# PCB-ATEM-GPITBO2.net
KiCad netlist of a schematic drawn in EAGLE
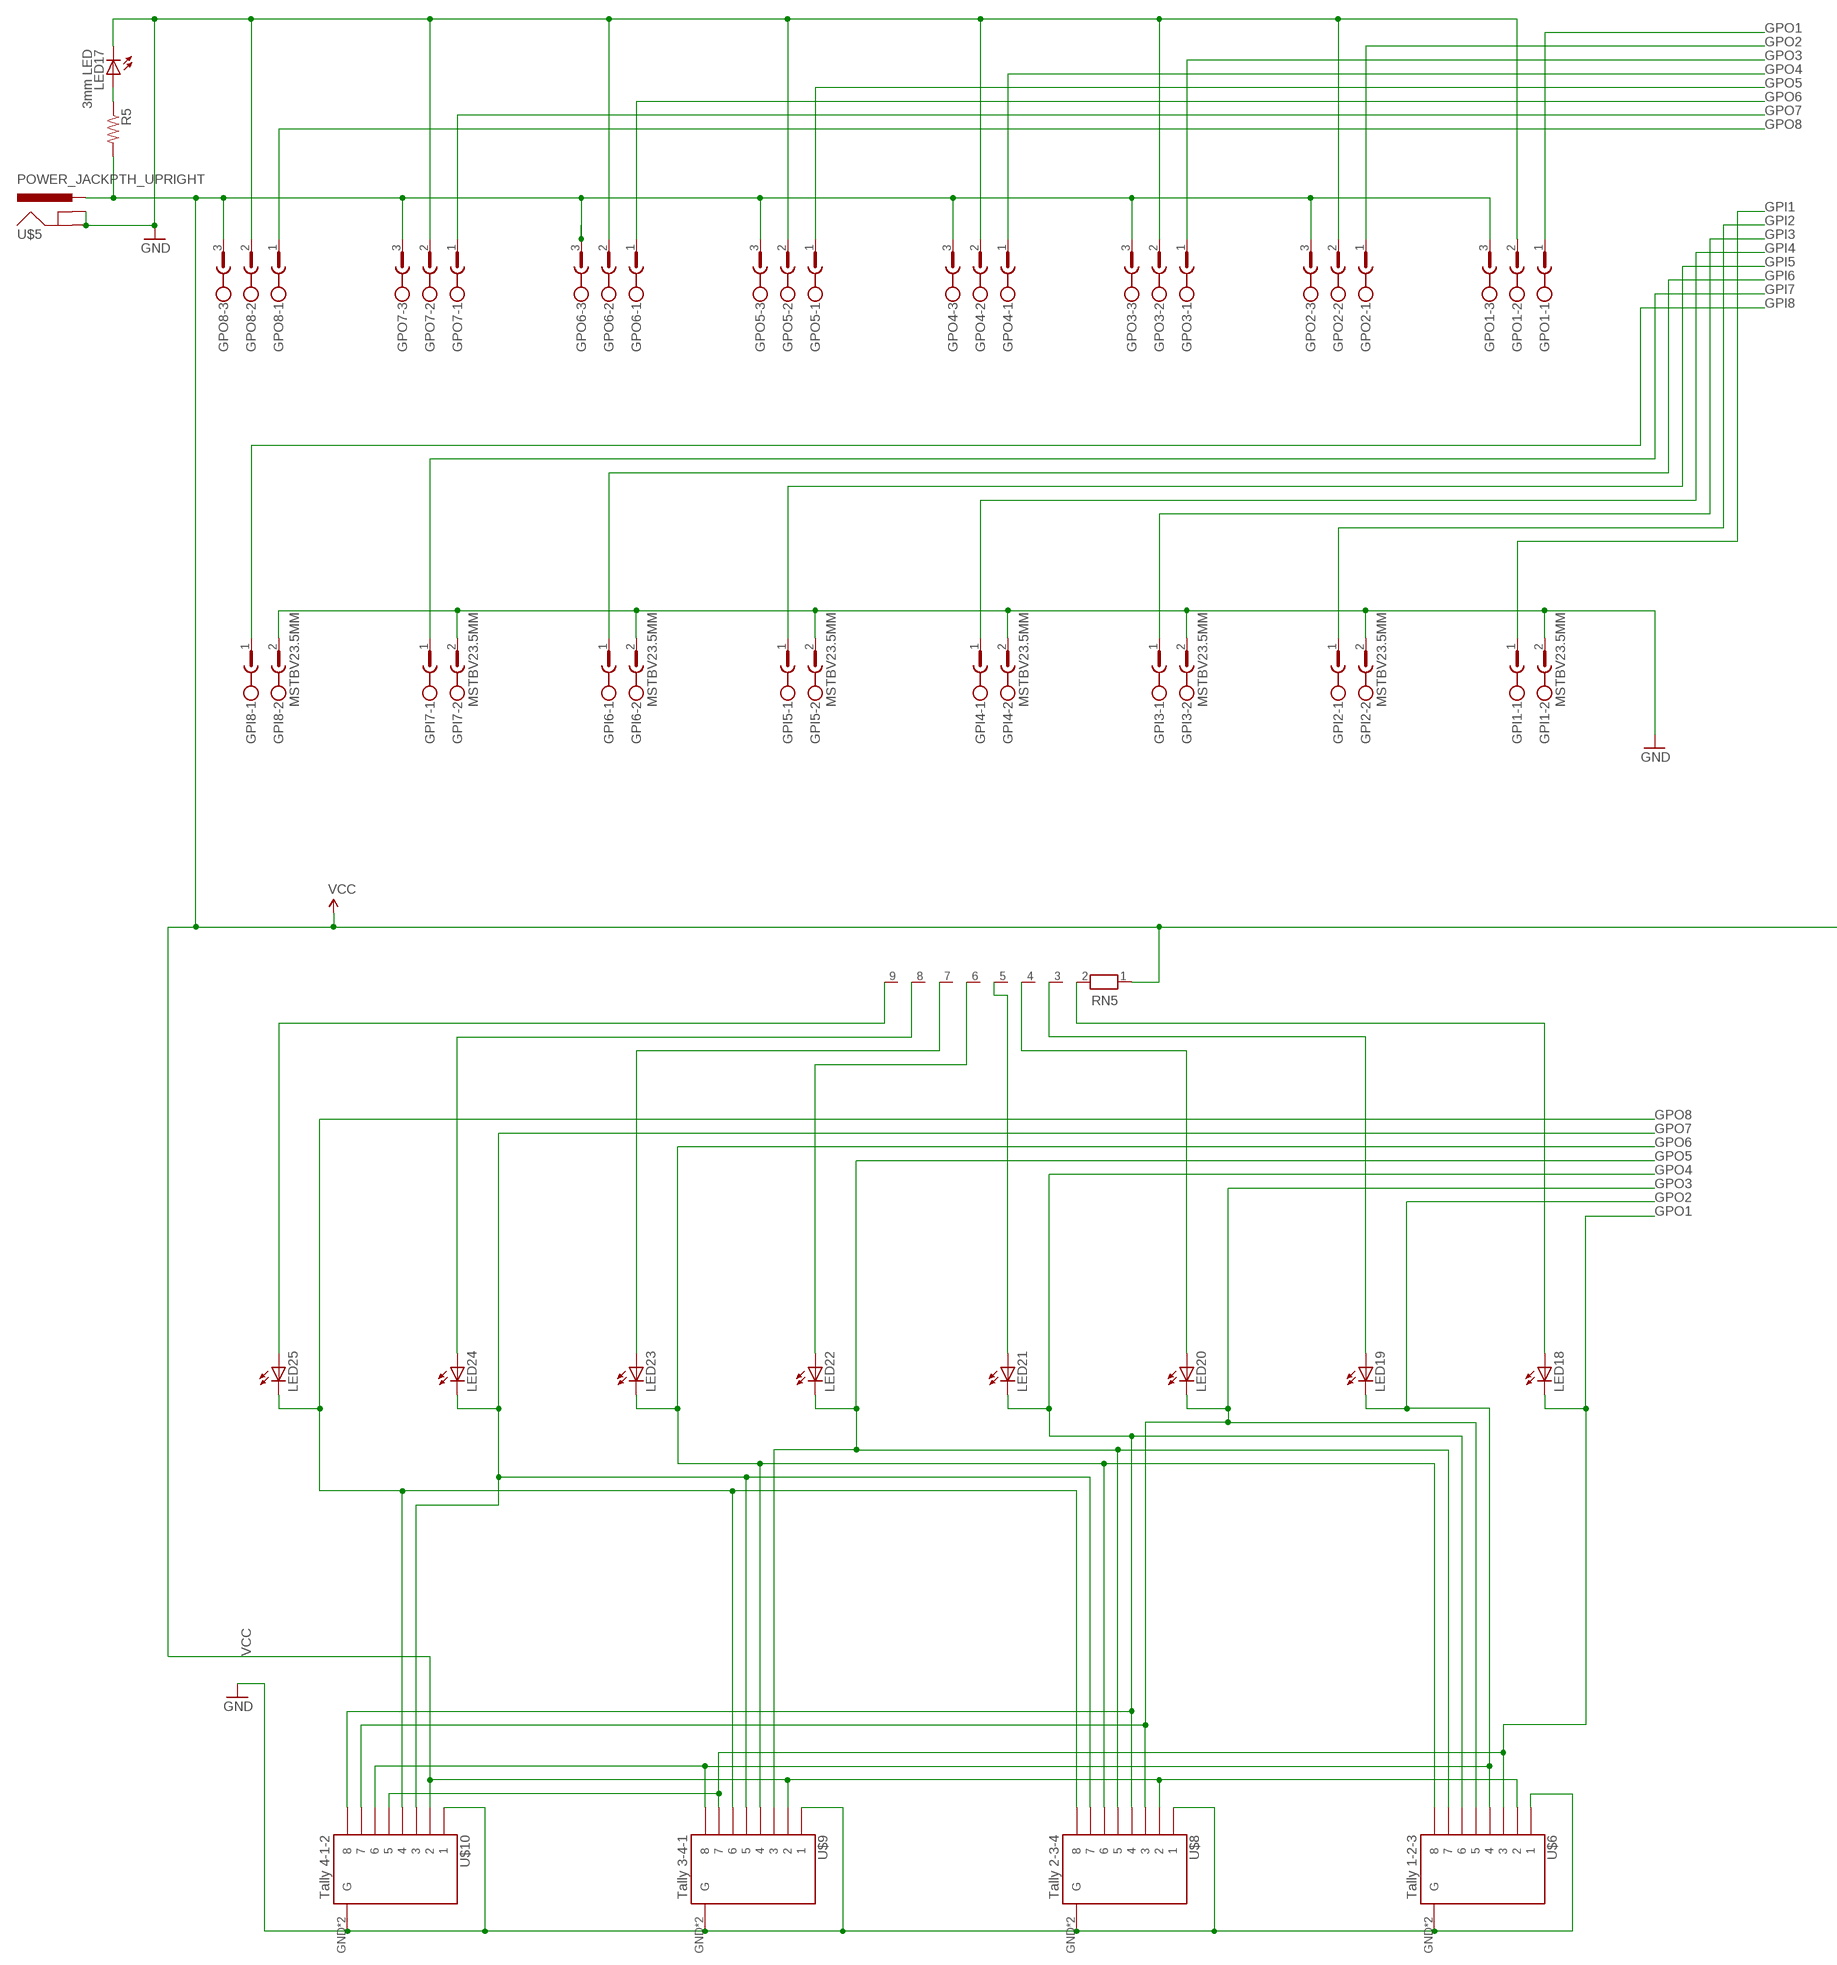
[diagram p0: schematic, sheet 1, part 1 of 2]
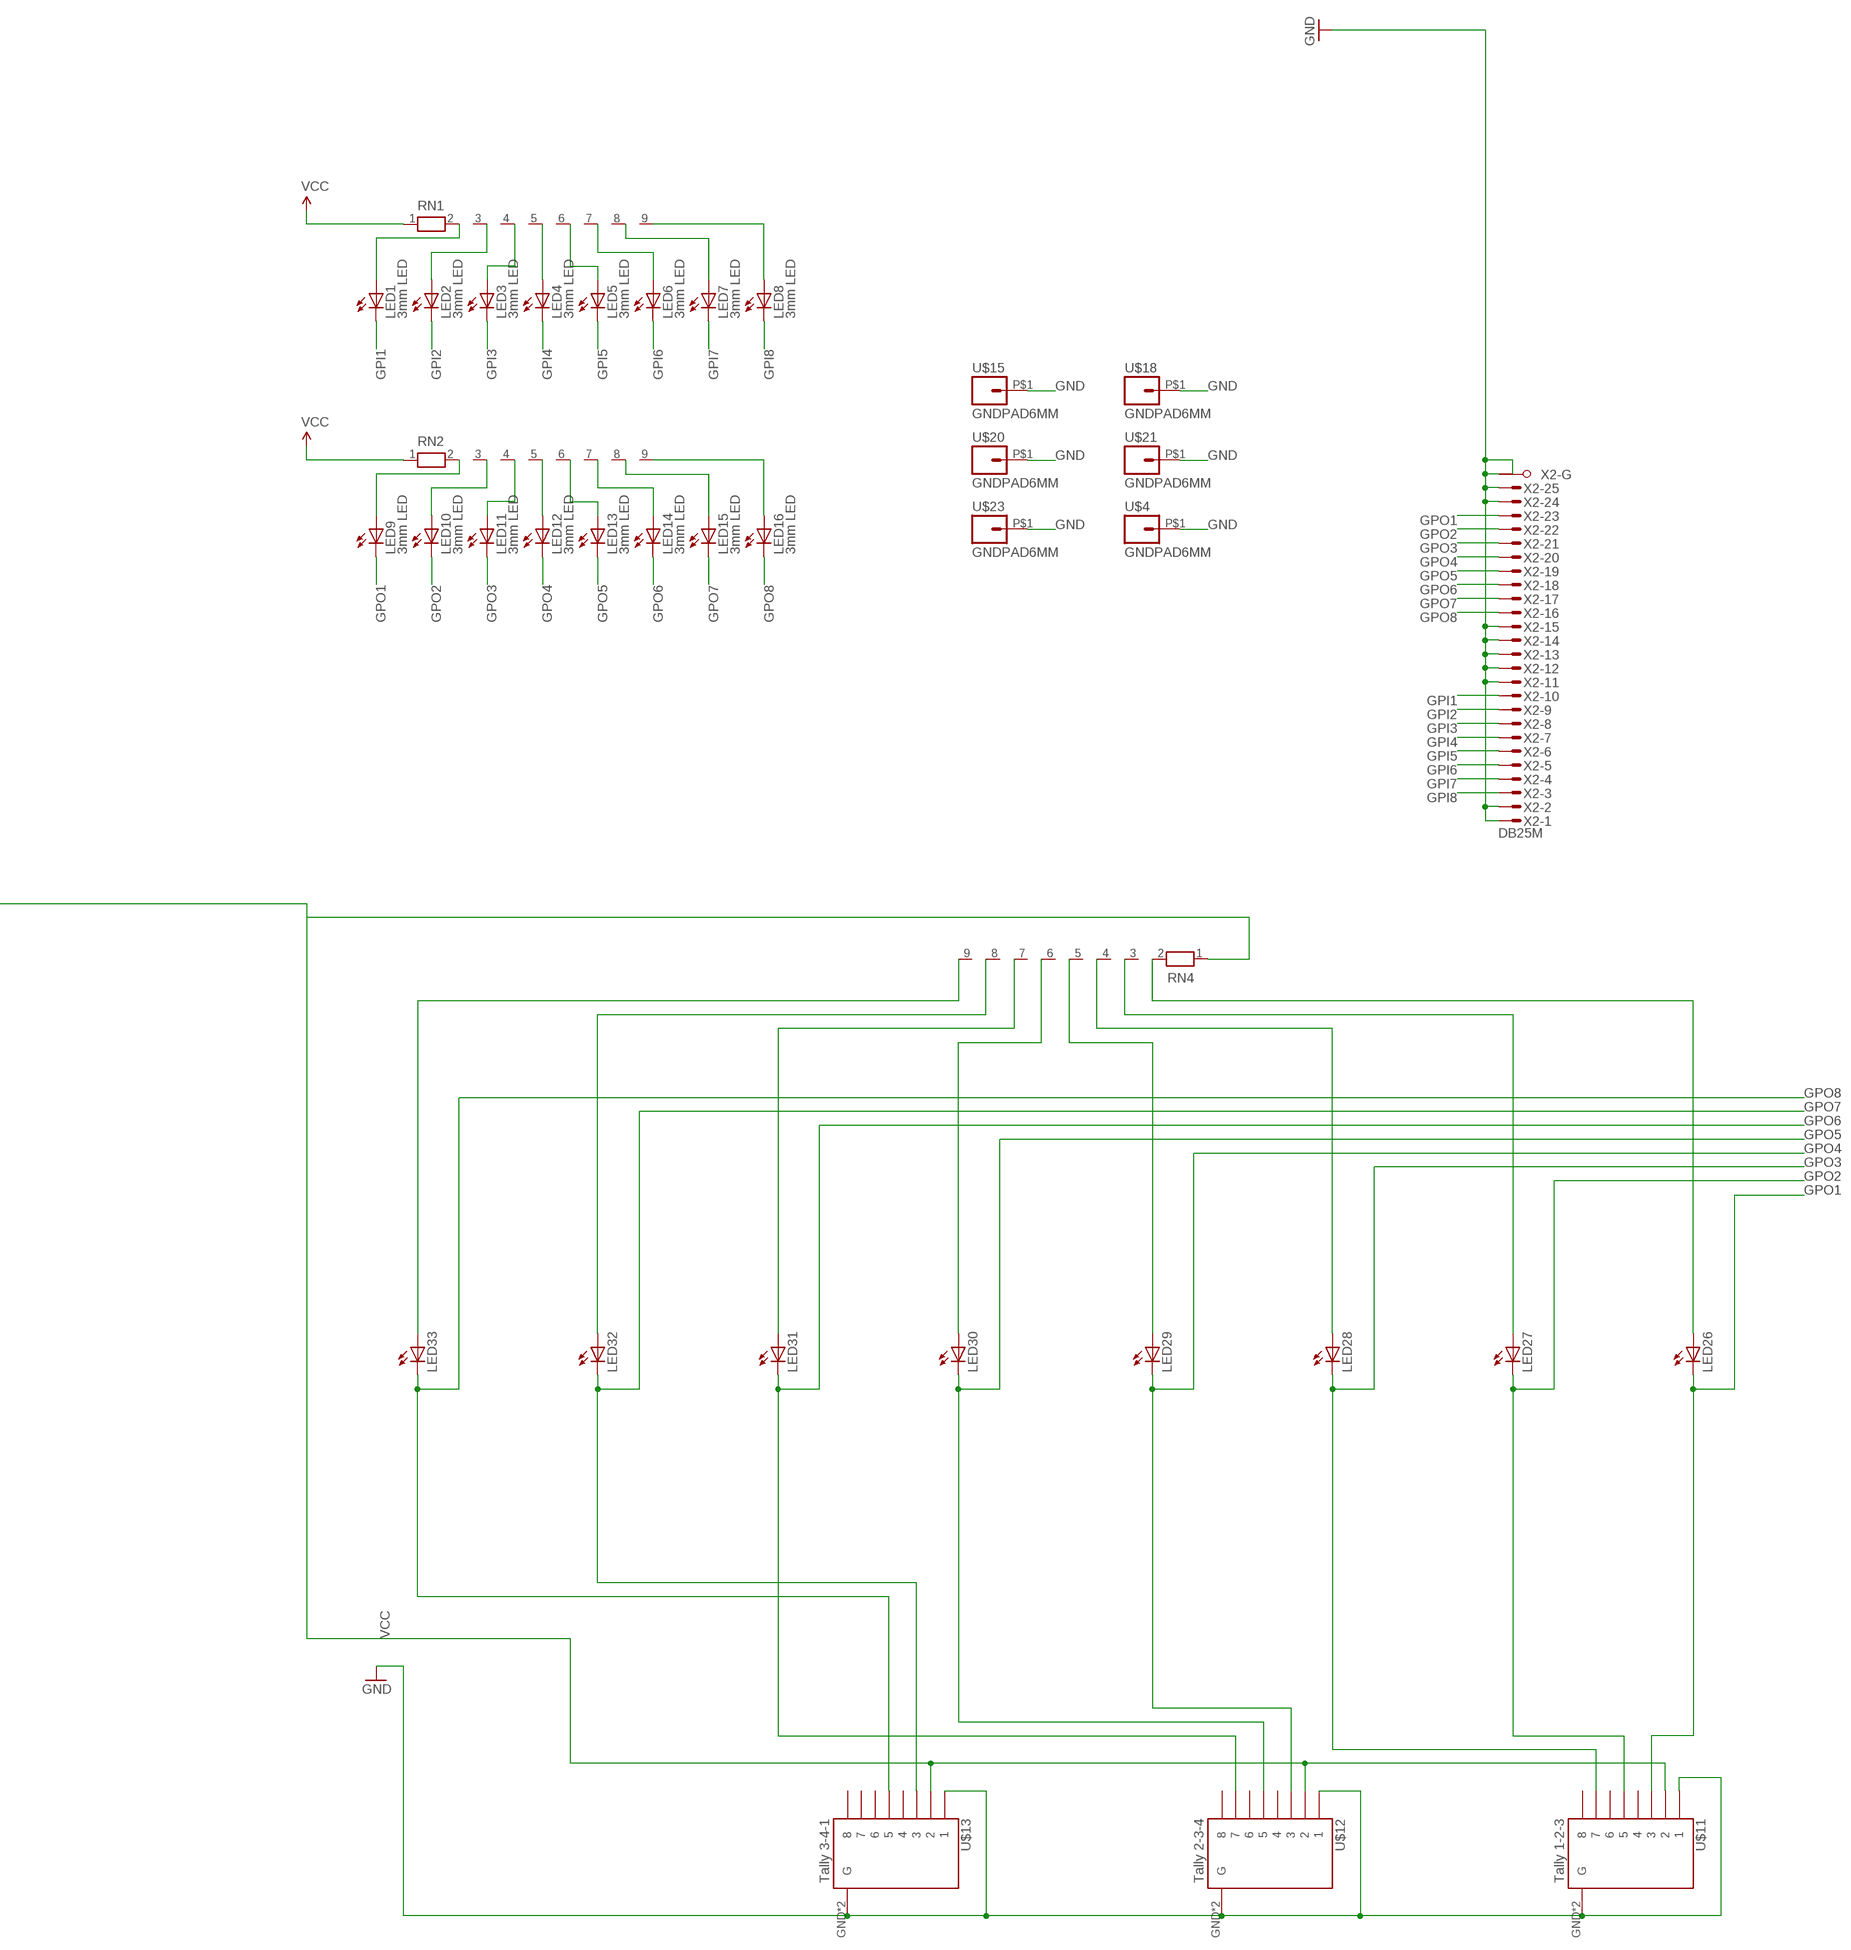
[diagram p1: schematic, sheet 1, part 2 of 2]

(export (version "E")
  (design (tool "Eeschema 10.0.6"))
  (components
    (comp (ref "GPI1")
      (value "MSTBV23.5MM")
      (footprint "eagle-import:MSTBV2-3.5")
      (libsource (lib "eagle-import") (part "MSTBV23.5MM"))
    )
    (comp (ref "GPI2")
      (value "MSTBV23.5MM")
      (footprint "eagle-import:MSTBV2-3.5")
      (libsource (lib "eagle-import") (part "MSTBV23.5MM"))
    )
    (comp (ref "GPI3")
      (value "MSTBV23.5MM")
      (footprint "eagle-import:MSTBV2-3.5")
      (libsource (lib "eagle-import") (part "MSTBV23.5MM"))
    )
    (comp (ref "GPI4")
      (value "MSTBV23.5MM")
      (footprint "eagle-import:MSTBV2-3.5")
      (libsource (lib "eagle-import") (part "MSTBV23.5MM"))
    )
    (comp (ref "GPI5")
      (value "MSTBV23.5MM")
      (footprint "eagle-import:MSTBV2-3.5")
      (libsource (lib "eagle-import") (part "MSTBV23.5MM"))
    )
    (comp (ref "GPI6")
      (value "MSTBV23.5MM")
      (footprint "eagle-import:MSTBV2-3.5")
      (libsource (lib "eagle-import") (part "MSTBV23.5MM"))
    )
    (comp (ref "GPI7")
      (value "MSTBV23.5MM")
      (footprint "eagle-import:MSTBV2-3.5")
      (libsource (lib "eagle-import") (part "MSTBV23.5MM"))
    )
    (comp (ref "GPI8")
      (value "MSTBV23.5MM")
      (footprint "eagle-import:MSTBV2-3.5")
      (libsource (lib "eagle-import") (part "MSTBV23.5MM"))
    )
    (comp (ref "GPO1")
      (value "CON1")
      (footprint "eagle-import:MSTBV3-3.5")
      (libsource (lib "eagle-import") (part "MSTBV33.5MM"))
    )
    (comp (ref "GPO2")
      (value "CON1")
      (footprint "eagle-import:MSTBV3-3.5")
      (libsource (lib "eagle-import") (part "MSTBV33.5MM"))
    )
    (comp (ref "GPO3")
      (value "CON1")
      (footprint "eagle-import:MSTBV3-3.5")
      (libsource (lib "eagle-import") (part "MSTBV33.5MM"))
    )
    (comp (ref "GPO4")
      (value "CON1")
      (footprint "eagle-import:MSTBV3-3.5")
      (libsource (lib "eagle-import") (part "MSTBV33.5MM"))
    )
    (comp (ref "GPO5")
      (value "CON1")
      (footprint "eagle-import:MSTBV3-3.5")
      (libsource (lib "eagle-import") (part "MSTBV33.5MM"))
    )
    (comp (ref "GPO6")
      (value "CON1")
      (footprint "eagle-import:MSTBV3-3.5")
      (libsource (lib "eagle-import") (part "MSTBV33.5MM"))
    )
    (comp (ref "GPO7")
      (value "CON1")
      (footprint "eagle-import:MSTBV3-3.5")
      (libsource (lib "eagle-import") (part "MSTBV33.5MM"))
    )
    (comp (ref "GPO8")
      (value "CON1")
      (footprint "eagle-import:MSTBV3-3.5")
      (libsource (lib "eagle-import") (part "MSTBV33.5MM"))
    )
    (comp (ref "LED1")
      (value "3mm LED")
      (footprint "eagle-import:LED3MM")
      (libsource (lib "eagle-import") (part "LED3MM"))
    )
    (comp (ref "LED2")
      (value "3mm LED")
      (footprint "eagle-import:LED3MM")
      (libsource (lib "eagle-import") (part "LED3MM"))
    )
    (comp (ref "LED3")
      (value "3mm LED")
      (footprint "eagle-import:LED3MM")
      (libsource (lib "eagle-import") (part "LED3MM"))
    )
    (comp (ref "LED4")
      (value "3mm LED")
      (footprint "eagle-import:LED3MM")
      (libsource (lib "eagle-import") (part "LED3MM"))
    )
    (comp (ref "LED5")
      (value "3mm LED")
      (footprint "eagle-import:LED3MM")
      (libsource (lib "eagle-import") (part "LED3MM"))
    )
    (comp (ref "LED6")
      (value "3mm LED")
      (footprint "eagle-import:LED3MM")
      (libsource (lib "eagle-import") (part "LED3MM"))
    )
    (comp (ref "LED7")
      (value "3mm LED")
      (footprint "eagle-import:LED3MM")
      (libsource (lib "eagle-import") (part "LED3MM"))
    )
    (comp (ref "LED8")
      (value "3mm LED")
      (footprint "eagle-import:LED3MM")
      (libsource (lib "eagle-import") (part "LED3MM"))
    )
    (comp (ref "LED9")
      (value "3mm LED")
      (footprint "eagle-import:LED3MM")
      (libsource (lib "eagle-import") (part "LED3MM"))
    )
    (comp (ref "LED10")
      (value "3mm LED")
      (footprint "eagle-import:LED3MM")
      (libsource (lib "eagle-import") (part "LED3MM"))
    )
    (comp (ref "LED11")
      (value "3mm LED")
      (footprint "eagle-import:LED3MM")
      (libsource (lib "eagle-import") (part "LED3MM"))
    )
    (comp (ref "LED12")
      (value "3mm LED")
      (footprint "eagle-import:LED3MM")
      (libsource (lib "eagle-import") (part "LED3MM"))
    )
    (comp (ref "LED13")
      (value "3mm LED")
      (footprint "eagle-import:LED3MM")
      (libsource (lib "eagle-import") (part "LED3MM"))
    )
    (comp (ref "LED14")
      (value "3mm LED")
      (footprint "eagle-import:LED3MM")
      (libsource (lib "eagle-import") (part "LED3MM"))
    )
    (comp (ref "LED15")
      (value "3mm LED")
      (footprint "eagle-import:LED3MM")
      (libsource (lib "eagle-import") (part "LED3MM"))
    )
    (comp (ref "LED16")
      (value "3mm LED")
      (footprint "eagle-import:LED3MM")
      (libsource (lib "eagle-import") (part "LED3MM"))
    )
    (comp (ref "LED17")
      (value "3mm LED")
      (footprint "eagle-import:LED3MM")
      (libsource (lib "eagle-import") (part "LED3MM"))
    )
    (comp (ref "LED18")
      (value "LED3MM")
      (footprint "eagle-import:LED3MM")
      (libsource (lib "eagle-import") (part "led_LED3MM"))
    )
    (comp (ref "LED19")
      (value "LED3MM")
      (footprint "eagle-import:LED3MM")
      (libsource (lib "eagle-import") (part "led_LED3MM"))
    )
    (comp (ref "LED20")
      (value "LED3MM")
      (footprint "eagle-import:LED3MM")
      (libsource (lib "eagle-import") (part "led_LED3MM"))
    )
    (comp (ref "LED21")
      (value "LED3MM")
      (footprint "eagle-import:LED3MM")
      (libsource (lib "eagle-import") (part "led_LED3MM"))
    )
    (comp (ref "LED22")
      (value "LED3MM")
      (footprint "eagle-import:LED3MM")
      (libsource (lib "eagle-import") (part "led_LED3MM"))
    )
    (comp (ref "LED23")
      (value "LED3MM")
      (footprint "eagle-import:LED3MM")
      (libsource (lib "eagle-import") (part "led_LED3MM"))
    )
    (comp (ref "LED24")
      (value "LED3MM")
      (footprint "eagle-import:LED3MM")
      (libsource (lib "eagle-import") (part "led_LED3MM"))
    )
    (comp (ref "LED25")
      (value "LED3MM")
      (footprint "eagle-import:LED3MM")
      (libsource (lib "eagle-import") (part "led_LED3MM"))
    )
    (comp (ref "LED26")
      (value "LED3MM")
      (footprint "eagle-import:LED3MM")
      (libsource (lib "eagle-import") (part "led_LED3MM"))
    )
    (comp (ref "LED27")
      (value "LED3MM")
      (footprint "eagle-import:LED3MM")
      (libsource (lib "eagle-import") (part "led_LED3MM"))
    )
    (comp (ref "LED28")
      (value "LED3MM")
      (footprint "eagle-import:LED3MM")
      (libsource (lib "eagle-import") (part "led_LED3MM"))
    )
    (comp (ref "LED29")
      (value "LED3MM")
      (footprint "eagle-import:LED3MM")
      (libsource (lib "eagle-import") (part "led_LED3MM"))
    )
    (comp (ref "LED30")
      (value "LED3MM")
      (footprint "eagle-import:LED3MM")
      (libsource (lib "eagle-import") (part "led_LED3MM"))
    )
    (comp (ref "LED31")
      (value "LED3MM")
      (footprint "eagle-import:LED3MM")
      (libsource (lib "eagle-import") (part "led_LED3MM"))
    )
    (comp (ref "LED32")
      (value "LED3MM")
      (footprint "eagle-import:LED3MM")
      (libsource (lib "eagle-import") (part "led_LED3MM"))
    )
    (comp (ref "LED33")
      (value "LED3MM")
      (footprint "eagle-import:LED3MM")
      (libsource (lib "eagle-import") (part "led_LED3MM"))
    )
    (comp (ref "R5")
      (value "RESISTOR0603-RES")
      (footprint "eagle-import:0603-RES")
      (libsource (lib "eagle-import") (part "RESISTOR0603-RES"))
    )
    (comp (ref "RN1")
      (value "RN08")
      (footprint "eagle-import:RN-9")
      (libsource (lib "eagle-import") (part "RN08"))
    )
    (comp (ref "RN2")
      (value "RN08")
      (footprint "eagle-import:RN-9")
      (libsource (lib "eagle-import") (part "RN08"))
    )
    (comp (ref "RN4")
      (value "RN08")
      (footprint "eagle-import:RN-9")
      (libsource (lib "eagle-import") (part "RN08"))
    )
    (comp (ref "RN5")
      (value "RN08")
      (footprint "eagle-import:RN-9")
      (libsource (lib "eagle-import") (part "RN08"))
    )
    (comp (ref "U$4")
      (value "GNDPAD6MM")
      (footprint "eagle-import:3.2MMPAD6MM")
      (libsource (lib "eagle-import") (part "GNDPAD6MM"))
    )
    (comp (ref "U$5")
      (value "POWER_JACKPTH_UPRIGHT")
      (footprint "eagle-import:POWER_JACK_PTH_UPRIGHT")
      (libsource (lib "eagle-import") (part "POWER_JACKPTH_UPRIGHT"))
    )
    (comp (ref "U$6")
      (value "Tally 1-2-3")
      (footprint "eagle-import:RJ45-8_GND_UPRIGHT")
      (libsource (lib "eagle-import") (part "RJ45-8_GNDUPRIGHT"))
    )
    (comp (ref "U$8")
      (value "Tally 2-3-4")
      (footprint "eagle-import:RJ45-8_GND_UPRIGHT")
      (libsource (lib "eagle-import") (part "RJ45-8_GNDUPRIGHT"))
    )
    (comp (ref "U$9")
      (value "Tally 3-4-1")
      (footprint "eagle-import:RJ45-8_GND_UPRIGHT")
      (libsource (lib "eagle-import") (part "RJ45-8_GNDUPRIGHT"))
    )
    (comp (ref "U$10")
      (value "Tally 4-1-2")
      (footprint "eagle-import:RJ45-8_GND_UPRIGHT")
      (libsource (lib "eagle-import") (part "RJ45-8_GNDUPRIGHT"))
    )
    (comp (ref "U$11")
      (value "Tally 1-2-3")
      (footprint "eagle-import:RJ45-8_GND_UPRIGHT")
      (libsource (lib "eagle-import") (part "RJ45-8_GNDUPRIGHT"))
    )
    (comp (ref "U$12")
      (value "Tally 2-3-4")
      (footprint "eagle-import:RJ45-8_GND_UPRIGHT")
      (libsource (lib "eagle-import") (part "RJ45-8_GNDUPRIGHT"))
    )
    (comp (ref "U$13")
      (value "Tally 3-4-1")
      (footprint "eagle-import:RJ45-8_GND_UPRIGHT")
      (libsource (lib "eagle-import") (part "RJ45-8_GNDUPRIGHT"))
    )
    (comp (ref "U$15")
      (value "GNDPAD6MM")
      (footprint "eagle-import:3.2MMPAD6MM")
      (libsource (lib "eagle-import") (part "GNDPAD6MM"))
    )
    (comp (ref "U$18")
      (value "GNDPAD6MM")
      (footprint "eagle-import:3.2MMPAD6MM")
      (libsource (lib "eagle-import") (part "GNDPAD6MM"))
    )
    (comp (ref "U$20")
      (value "GNDPAD6MM")
      (footprint "eagle-import:3.2MMPAD6MM")
      (libsource (lib "eagle-import") (part "GNDPAD6MM"))
    )
    (comp (ref "U$21")
      (value "GNDPAD6MM")
      (footprint "eagle-import:3.2MMPAD6MM")
      (libsource (lib "eagle-import") (part "GNDPAD6MM"))
    )
    (comp (ref "U$23")
      (value "GNDPAD6MM")
      (footprint "eagle-import:3.2MMPAD6MM")
      (libsource (lib "eagle-import") (part "GNDPAD6MM"))
    )
    (comp (ref "X2")
      (value "DB25M")
      (footprint "eagle-import:M25HP")
      (libsource (lib "eagle-import") (part "M25HPS"))
    )
  )
  (nets
    (net (code "1") (name "GND") (class "Default")
      (node (ref "GPI1") (pin "2") (pinfunction "1_2") (pintype "passive"))
      (node (ref "GPI2") (pin "2") (pinfunction "1_2") (pintype "passive"))
      (node (ref "GPI3") (pin "2") (pinfunction "1_2") (pintype "passive"))
      (node (ref "GPI4") (pin "2") (pinfunction "1_2") (pintype "passive"))
      (node (ref "GPI5") (pin "2") (pinfunction "1_2") (pintype "passive"))
      (node (ref "GPI6") (pin "2") (pinfunction "1_2") (pintype "passive"))
      (node (ref "GPI7") (pin "2") (pinfunction "1_2") (pintype "passive"))
      (node (ref "GPI8") (pin "2") (pinfunction "1_2") (pintype "passive"))
      (node (ref "GPO1") (pin "2") (pinfunction "1_2") (pintype "passive"))
      (node (ref "GPO2") (pin "2") (pinfunction "1_2") (pintype "passive"))
      (node (ref "GPO3") (pin "2") (pinfunction "1_2") (pintype "passive"))
      (node (ref "GPO4") (pin "2") (pinfunction "1_2") (pintype "passive"))
      (node (ref "GPO5") (pin "2") (pinfunction "1_2") (pintype "passive"))
      (node (ref "GPO6") (pin "2") (pinfunction "1_2") (pintype "passive"))
      (node (ref "GPO7") (pin "2") (pinfunction "1_2") (pintype "passive"))
      (node (ref "GPO8") (pin "2") (pinfunction "1_2") (pintype "passive"))
      (node (ref "LED17") (pin "K") (pinfunction "C_K") (pintype "passive"))
      (node (ref "U$10") (pin "1") (pinfunction "1_1") (pintype "bidirectional"))
      (node (ref "U$10") (pin "GND") (pinfunction "G_GND") (pintype "power_in"))
      (node (ref "U$10") (pin "GND1") (pinfunction "G_GND1") (pintype "power_in"))
      (node (ref "U$11") (pin "1") (pinfunction "1_1") (pintype "bidirectional"))
      (node (ref "U$11") (pin "GND") (pinfunction "G_GND") (pintype "power_in"))
      (node (ref "U$11") (pin "GND1") (pinfunction "G_GND1") (pintype "power_in"))
      (node (ref "U$12") (pin "1") (pinfunction "1_1") (pintype "bidirectional"))
      (node (ref "U$12") (pin "GND") (pinfunction "G_GND") (pintype "power_in"))
      (node (ref "U$12") (pin "GND1") (pinfunction "G_GND1") (pintype "power_in"))
      (node (ref "U$13") (pin "1") (pinfunction "1_1") (pintype "bidirectional"))
      (node (ref "U$13") (pin "GND") (pinfunction "G_GND") (pintype "power_in"))
      (node (ref "U$13") (pin "GND1") (pinfunction "G_GND1") (pintype "power_in"))
      (node (ref "U$15") (pin "P$1") (pinfunction "1_P$1") (pintype "passive"))
      (node (ref "U$18") (pin "P$1") (pinfunction "1_P$1") (pintype "passive"))
      (node (ref "U$20") (pin "P$1") (pinfunction "1_P$1") (pintype "passive"))
      (node (ref "U$21") (pin "P$1") (pinfunction "1_P$1") (pintype "passive"))
      (node (ref "U$23") (pin "P$1") (pinfunction "1_P$1") (pintype "passive"))
      (node (ref "U$4") (pin "P$1") (pinfunction "1_P$1") (pintype "passive"))
      (node (ref "U$5") (pin "GND") (pinfunction "GND_GND") (pintype "bidirectional"))
      (node (ref "U$5") (pin "SHUNT") (pinfunction "GNDBREAK_SHUNT") (pintype "bidirectional"))
      (node (ref "U$6") (pin "1") (pinfunction "1_1") (pintype "bidirectional"))
      (node (ref "U$6") (pin "GND") (pinfunction "G_GND") (pintype "power_in"))
      (node (ref "U$6") (pin "GND1") (pinfunction "G_GND1") (pintype "power_in"))
      (node (ref "U$8") (pin "1") (pinfunction "1_1") (pintype "bidirectional"))
      (node (ref "U$8") (pin "GND") (pinfunction "G_GND") (pintype "power_in"))
      (node (ref "U$8") (pin "GND1") (pinfunction "G_GND1") (pintype "power_in"))
      (node (ref "U$9") (pin "1") (pinfunction "1_1") (pintype "bidirectional"))
      (node (ref "U$9") (pin "GND") (pinfunction "G_GND") (pintype "power_in"))
      (node (ref "U$9") (pin "GND1") (pinfunction "G_GND1") (pintype "power_in"))
      (node (ref "X2") (pin "1") (pinfunction "M_1") (pintype "passive"))
      (node (ref "X2") (pin "11") (pinfunction "M_11") (pintype "passive"))
      (node (ref "X2") (pin "12") (pinfunction "M_12") (pintype "passive"))
      (node (ref "X2") (pin "13") (pinfunction "M_13") (pintype "passive"))
      (node (ref "X2") (pin "14") (pinfunction "M_14") (pintype "passive"))
      (node (ref "X2") (pin "15") (pinfunction "M_15") (pintype "passive"))
      (node (ref "X2") (pin "2") (pinfunction "M_2") (pintype "passive"))
      (node (ref "X2") (pin "24") (pinfunction "M_24") (pintype "passive"))
      (node (ref "X2") (pin "25") (pinfunction "M_25") (pintype "passive"))
      (node (ref "X2") (pin "G1") (pinfunction "G1_G1") (pintype "passive"))
      (node (ref "X2") (pin "G2") (pinfunction "G2_G2") (pintype "passive"))
    )
    (net (code "2") (name "GPI1") (class "Default")
      (node (ref "GPI1") (pin "1") (pinfunction "1_1") (pintype "passive"))
      (node (ref "LED1") (pin "K") (pinfunction "C_K") (pintype "passive"))
      (node (ref "X2") (pin "10") (pinfunction "M_10") (pintype "passive"))
    )
    (net (code "3") (name "GPI2") (class "Default")
      (node (ref "GPI2") (pin "1") (pinfunction "1_1") (pintype "passive"))
      (node (ref "LED2") (pin "K") (pinfunction "C_K") (pintype "passive"))
      (node (ref "X2") (pin "9") (pinfunction "M_9") (pintype "passive"))
    )
    (net (code "4") (name "GPI3") (class "Default")
      (node (ref "GPI3") (pin "1") (pinfunction "1_1") (pintype "passive"))
      (node (ref "LED3") (pin "K") (pinfunction "C_K") (pintype "passive"))
      (node (ref "X2") (pin "8") (pinfunction "M_8") (pintype "passive"))
    )
    (net (code "5") (name "GPI4") (class "Default")
      (node (ref "GPI4") (pin "1") (pinfunction "1_1") (pintype "passive"))
      (node (ref "LED4") (pin "K") (pinfunction "C_K") (pintype "passive"))
      (node (ref "X2") (pin "7") (pinfunction "M_7") (pintype "passive"))
    )
    (net (code "6") (name "GPI5") (class "Default")
      (node (ref "GPI5") (pin "1") (pinfunction "1_1") (pintype "passive"))
      (node (ref "LED5") (pin "K") (pinfunction "C_K") (pintype "passive"))
      (node (ref "X2") (pin "6") (pinfunction "M_6") (pintype "passive"))
    )
    (net (code "7") (name "GPI6") (class "Default")
      (node (ref "GPI6") (pin "1") (pinfunction "1_1") (pintype "passive"))
      (node (ref "LED6") (pin "K") (pinfunction "C_K") (pintype "passive"))
      (node (ref "X2") (pin "5") (pinfunction "M_5") (pintype "passive"))
    )
    (net (code "8") (name "GPI7") (class "Default")
      (node (ref "GPI7") (pin "1") (pinfunction "1_1") (pintype "passive"))
      (node (ref "LED7") (pin "K") (pinfunction "C_K") (pintype "passive"))
      (node (ref "X2") (pin "4") (pinfunction "M_4") (pintype "passive"))
    )
    (net (code "9") (name "GPI8") (class "Default")
      (node (ref "GPI8") (pin "1") (pinfunction "1_1") (pintype "passive"))
      (node (ref "LED8") (pin "K") (pinfunction "C_K") (pintype "passive"))
      (node (ref "X2") (pin "3") (pinfunction "M_3") (pintype "passive"))
    )
    (net (code "10") (name "GPO1") (class "Default")
      (node (ref "GPO1") (pin "1") (pinfunction "1_1") (pintype "passive"))
      (node (ref "LED18") (pin "K") (pinfunction "C_K") (pintype "passive"))
      (node (ref "LED26") (pin "K") (pinfunction "C_K") (pintype "passive"))
      (node (ref "LED9") (pin "K") (pinfunction "C_K") (pintype "passive"))
      (node (ref "U$10") (pin "5") (pinfunction "5_5") (pintype "bidirectional"))
      (node (ref "U$11") (pin "3") (pinfunction "3_3") (pintype "bidirectional"))
      (node (ref "U$6") (pin "3") (pinfunction "3_3") (pintype "bidirectional"))
      (node (ref "U$9") (pin "7") (pinfunction "7_7") (pintype "bidirectional"))
      (node (ref "X2") (pin "23") (pinfunction "M_23") (pintype "passive"))
    )
    (net (code "11") (name "GPO2") (class "Default")
      (node (ref "GPO2") (pin "1") (pinfunction "1_1") (pintype "passive"))
      (node (ref "LED10") (pin "K") (pinfunction "C_K") (pintype "passive"))
      (node (ref "LED19") (pin "K") (pinfunction "C_K") (pintype "passive"))
      (node (ref "LED27") (pin "K") (pinfunction "C_K") (pintype "passive"))
      (node (ref "U$10") (pin "6") (pinfunction "6_6") (pintype "bidirectional"))
      (node (ref "U$11") (pin "5") (pinfunction "5_5") (pintype "bidirectional"))
      (node (ref "U$6") (pin "4") (pinfunction "4_4") (pintype "bidirectional"))
      (node (ref "U$9") (pin "8") (pinfunction "8_8") (pintype "bidirectional"))
      (node (ref "X2") (pin "22") (pinfunction "M_22") (pintype "passive"))
    )
    (net (code "12") (name "GPO3") (class "Default")
      (node (ref "GPO3") (pin "1") (pinfunction "1_1") (pintype "passive"))
      (node (ref "LED11") (pin "K") (pinfunction "C_K") (pintype "passive"))
      (node (ref "LED20") (pin "K") (pinfunction "C_K") (pintype "passive"))
      (node (ref "LED28") (pin "K") (pinfunction "C_K") (pintype "passive"))
      (node (ref "U$10") (pin "7") (pinfunction "7_7") (pintype "bidirectional"))
      (node (ref "U$11") (pin "7") (pinfunction "7_7") (pintype "bidirectional"))
      (node (ref "U$6") (pin "5") (pinfunction "5_5") (pintype "bidirectional"))
      (node (ref "U$8") (pin "3") (pinfunction "3_3") (pintype "bidirectional"))
      (node (ref "X2") (pin "21") (pinfunction "M_21") (pintype "passive"))
    )
    (net (code "13") (name "GPO4") (class "Default")
      (node (ref "GPO4") (pin "1") (pinfunction "1_1") (pintype "passive"))
      (node (ref "LED12") (pin "K") (pinfunction "C_K") (pintype "passive"))
      (node (ref "LED21") (pin "K") (pinfunction "C_K") (pintype "passive"))
      (node (ref "LED29") (pin "K") (pinfunction "C_K") (pintype "passive"))
      (node (ref "U$10") (pin "8") (pinfunction "8_8") (pintype "bidirectional"))
      (node (ref "U$12") (pin "3") (pinfunction "3_3") (pintype "bidirectional"))
      (node (ref "U$6") (pin "6") (pinfunction "6_6") (pintype "bidirectional"))
      (node (ref "U$8") (pin "4") (pinfunction "4_4") (pintype "bidirectional"))
      (node (ref "X2") (pin "20") (pinfunction "M_20") (pintype "passive"))
    )
    (net (code "14") (name "GPO5") (class "Default")
      (node (ref "GPO5") (pin "1") (pinfunction "1_1") (pintype "passive"))
      (node (ref "LED13") (pin "K") (pinfunction "C_K") (pintype "passive"))
      (node (ref "LED22") (pin "K") (pinfunction "C_K") (pintype "passive"))
      (node (ref "LED30") (pin "K") (pinfunction "C_K") (pintype "passive"))
      (node (ref "U$12") (pin "5") (pinfunction "5_5") (pintype "bidirectional"))
      (node (ref "U$6") (pin "7") (pinfunction "7_7") (pintype "bidirectional"))
      (node (ref "U$8") (pin "5") (pinfunction "5_5") (pintype "bidirectional"))
      (node (ref "U$9") (pin "3") (pinfunction "3_3") (pintype "bidirectional"))
      (node (ref "X2") (pin "19") (pinfunction "M_19") (pintype "passive"))
    )
    (net (code "15") (name "GPO6") (class "Default")
      (node (ref "GPO6") (pin "1") (pinfunction "1_1") (pintype "passive"))
      (node (ref "LED14") (pin "K") (pinfunction "C_K") (pintype "passive"))
      (node (ref "LED23") (pin "K") (pinfunction "C_K") (pintype "passive"))
      (node (ref "LED31") (pin "K") (pinfunction "C_K") (pintype "passive"))
      (node (ref "U$12") (pin "7") (pinfunction "7_7") (pintype "bidirectional"))
      (node (ref "U$6") (pin "8") (pinfunction "8_8") (pintype "bidirectional"))
      (node (ref "U$8") (pin "6") (pinfunction "6_6") (pintype "bidirectional"))
      (node (ref "U$9") (pin "4") (pinfunction "4_4") (pintype "bidirectional"))
      (node (ref "X2") (pin "18") (pinfunction "M_18") (pintype "passive"))
    )
    (net (code "16") (name "GPO7") (class "Default")
      (node (ref "GPO7") (pin "1") (pinfunction "1_1") (pintype "passive"))
      (node (ref "LED15") (pin "K") (pinfunction "C_K") (pintype "passive"))
      (node (ref "LED24") (pin "K") (pinfunction "C_K") (pintype "passive"))
      (node (ref "LED32") (pin "K") (pinfunction "C_K") (pintype "passive"))
      (node (ref "U$10") (pin "3") (pinfunction "3_3") (pintype "bidirectional"))
      (node (ref "U$13") (pin "3") (pinfunction "3_3") (pintype "bidirectional"))
      (node (ref "U$8") (pin "7") (pinfunction "7_7") (pintype "bidirectional"))
      (node (ref "U$9") (pin "5") (pinfunction "5_5") (pintype "bidirectional"))
      (node (ref "X2") (pin "17") (pinfunction "M_17") (pintype "passive"))
    )
    (net (code "17") (name "GPO8") (class "Default")
      (node (ref "GPO8") (pin "1") (pinfunction "1_1") (pintype "passive"))
      (node (ref "LED16") (pin "K") (pinfunction "C_K") (pintype "passive"))
      (node (ref "LED25") (pin "K") (pinfunction "C_K") (pintype "passive"))
      (node (ref "LED33") (pin "K") (pinfunction "C_K") (pintype "passive"))
      (node (ref "U$10") (pin "4") (pinfunction "4_4") (pintype "bidirectional"))
      (node (ref "U$13") (pin "5") (pinfunction "5_5") (pintype "bidirectional"))
      (node (ref "U$8") (pin "8") (pinfunction "8_8") (pintype "bidirectional"))
      (node (ref "U$9") (pin "6") (pinfunction "6_6") (pintype "bidirectional"))
      (node (ref "X2") (pin "16") (pinfunction "M_16") (pintype "passive"))
    )
    (net (code "18") (name "Net-(LED1-PadA)") (class "Default")
      (node (ref "LED1") (pin "A") (pinfunction "A_A") (pintype "passive"))
      (node (ref "RN1") (pin "2") (pinfunction "2_2") (pintype "passive"))
    )
    (net (code "19") (name "Net-(LED2-PadA)") (class "Default")
      (node (ref "LED2") (pin "A") (pinfunction "A_A") (pintype "passive"))
      (node (ref "RN1") (pin "3") (pinfunction "3_3") (pintype "passive"))
    )
    (net (code "20") (name "Net-(LED3-PadA)") (class "Default")
      (node (ref "LED3") (pin "A") (pinfunction "A_A") (pintype "passive"))
      (node (ref "RN1") (pin "4") (pinfunction "4_4") (pintype "passive"))
    )
    (net (code "21") (name "Net-(LED4-PadA)") (class "Default")
      (node (ref "LED4") (pin "A") (pinfunction "A_A") (pintype "passive"))
      (node (ref "RN1") (pin "5") (pinfunction "5_5") (pintype "passive"))
    )
    (net (code "22") (name "Net-(LED5-PadA)") (class "Default")
      (node (ref "LED5") (pin "A") (pinfunction "A_A") (pintype "passive"))
      (node (ref "RN1") (pin "6") (pinfunction "6_6") (pintype "passive"))
    )
    (net (code "23") (name "Net-(LED6-PadA)") (class "Default")
      (node (ref "LED6") (pin "A") (pinfunction "A_A") (pintype "passive"))
      (node (ref "RN1") (pin "7") (pinfunction "7_7") (pintype "passive"))
    )
    (net (code "24") (name "Net-(LED7-PadA)") (class "Default")
      (node (ref "LED7") (pin "A") (pinfunction "A_A") (pintype "passive"))
      (node (ref "RN1") (pin "8") (pinfunction "8_8") (pintype "passive"))
    )
    (net (code "25") (name "Net-(LED8-PadA)") (class "Default")
      (node (ref "LED8") (pin "A") (pinfunction "A_A") (pintype "passive"))
      (node (ref "RN1") (pin "9") (pinfunction "9_9") (pintype "passive"))
    )
    (net (code "26") (name "Net-(LED9-PadA)") (class "Default")
      (node (ref "LED9") (pin "A") (pinfunction "A_A") (pintype "passive"))
      (node (ref "RN2") (pin "2") (pinfunction "2_2") (pintype "passive"))
    )
    (net (code "27") (name "Net-(LED10-PadA)") (class "Default")
      (node (ref "LED10") (pin "A") (pinfunction "A_A") (pintype "passive"))
      (node (ref "RN2") (pin "3") (pinfunction "3_3") (pintype "passive"))
    )
    (net (code "28") (name "Net-(LED11-PadA)") (class "Default")
      (node (ref "LED11") (pin "A") (pinfunction "A_A") (pintype "passive"))
      (node (ref "RN2") (pin "4") (pinfunction "4_4") (pintype "passive"))
    )
    (net (code "29") (name "Net-(LED12-PadA)") (class "Default")
      (node (ref "LED12") (pin "A") (pinfunction "A_A") (pintype "passive"))
      (node (ref "RN2") (pin "5") (pinfunction "5_5") (pintype "passive"))
    )
    (net (code "30") (name "Net-(LED13-PadA)") (class "Default")
      (node (ref "LED13") (pin "A") (pinfunction "A_A") (pintype "passive"))
      (node (ref "RN2") (pin "6") (pinfunction "6_6") (pintype "passive"))
    )
    (net (code "31") (name "Net-(LED14-PadA)") (class "Default")
      (node (ref "LED14") (pin "A") (pinfunction "A_A") (pintype "passive"))
      (node (ref "RN2") (pin "7") (pinfunction "7_7") (pintype "passive"))
    )
    (net (code "32") (name "Net-(LED15-PadA)") (class "Default")
      (node (ref "LED15") (pin "A") (pinfunction "A_A") (pintype "passive"))
      (node (ref "RN2") (pin "8") (pinfunction "8_8") (pintype "passive"))
    )
    (net (code "33") (name "Net-(LED16-PadA)") (class "Default")
      (node (ref "LED16") (pin "A") (pinfunction "A_A") (pintype "passive"))
      (node (ref "RN2") (pin "9") (pinfunction "9_9") (pintype "passive"))
    )
    (net (code "34") (name "Net-(LED17-PadA)") (class "Default")
      (node (ref "LED17") (pin "A") (pinfunction "A_A") (pintype "passive"))
      (node (ref "R5") (pin "1") (pinfunction "1_1") (pintype "passive"))
    )
    (net (code "35") (name "Net-(LED18-PadA)") (class "Default")
      (node (ref "LED18") (pin "A") (pinfunction "A_A") (pintype "passive"))
      (node (ref "RN5") (pin "2") (pinfunction "2_2") (pintype "passive"))
    )
    (net (code "36") (name "Net-(LED19-PadA)") (class "Default")
      (node (ref "LED19") (pin "A") (pinfunction "A_A") (pintype "passive"))
      (node (ref "RN5") (pin "3") (pinfunction "3_3") (pintype "passive"))
    )
    (net (code "37") (name "Net-(LED20-PadA)") (class "Default")
      (node (ref "LED20") (pin "A") (pinfunction "A_A") (pintype "passive"))
      (node (ref "RN5") (pin "4") (pinfunction "4_4") (pintype "passive"))
    )
    (net (code "38") (name "Net-(LED21-PadA)") (class "Default")
      (node (ref "LED21") (pin "A") (pinfunction "A_A") (pintype "passive"))
      (node (ref "RN5") (pin "5") (pinfunction "5_5") (pintype "passive"))
    )
    (net (code "39") (name "Net-(LED22-PadA)") (class "Default")
      (node (ref "LED22") (pin "A") (pinfunction "A_A") (pintype "passive"))
      (node (ref "RN5") (pin "6") (pinfunction "6_6") (pintype "passive"))
    )
    (net (code "40") (name "Net-(LED23-PadA)") (class "Default")
      (node (ref "LED23") (pin "A") (pinfunction "A_A") (pintype "passive"))
      (node (ref "RN5") (pin "7") (pinfunction "7_7") (pintype "passive"))
    )
    (net (code "41") (name "Net-(LED24-PadA)") (class "Default")
      (node (ref "LED24") (pin "A") (pinfunction "A_A") (pintype "passive"))
      (node (ref "RN5") (pin "8") (pinfunction "8_8") (pintype "passive"))
    )
    (net (code "42") (name "Net-(LED25-PadA)") (class "Default")
      (node (ref "LED25") (pin "A") (pinfunction "A_A") (pintype "passive"))
      (node (ref "RN5") (pin "9") (pinfunction "9_9") (pintype "passive"))
    )
    (net (code "43") (name "Net-(LED26-PadA)") (class "Default")
      (node (ref "LED26") (pin "A") (pinfunction "A_A") (pintype "passive"))
      (node (ref "RN4") (pin "2") (pinfunction "2_2") (pintype "passive"))
    )
    (net (code "44") (name "Net-(LED27-PadA)") (class "Default")
      (node (ref "LED27") (pin "A") (pinfunction "A_A") (pintype "passive"))
      (node (ref "RN4") (pin "3") (pinfunction "3_3") (pintype "passive"))
    )
    (net (code "45") (name "Net-(LED28-PadA)") (class "Default")
      (node (ref "LED28") (pin "A") (pinfunction "A_A") (pintype "passive"))
      (node (ref "RN4") (pin "4") (pinfunction "4_4") (pintype "passive"))
    )
    (net (code "46") (name "Net-(LED29-PadA)") (class "Default")
      (node (ref "LED29") (pin "A") (pinfunction "A_A") (pintype "passive"))
      (node (ref "RN4") (pin "5") (pinfunction "5_5") (pintype "passive"))
    )
    (net (code "47") (name "Net-(LED30-PadA)") (class "Default")
      (node (ref "LED30") (pin "A") (pinfunction "A_A") (pintype "passive"))
      (node (ref "RN4") (pin "6") (pinfunction "6_6") (pintype "passive"))
    )
    (net (code "48") (name "Net-(LED31-PadA)") (class "Default")
      (node (ref "LED31") (pin "A") (pinfunction "A_A") (pintype "passive"))
      (node (ref "RN4") (pin "7") (pinfunction "7_7") (pintype "passive"))
    )
    (net (code "49") (name "Net-(LED32-PadA)") (class "Default")
      (node (ref "LED32") (pin "A") (pinfunction "A_A") (pintype "passive"))
      (node (ref "RN4") (pin "8") (pinfunction "8_8") (pintype "passive"))
    )
    (net (code "50") (name "Net-(LED33-PadA)") (class "Default")
      (node (ref "LED33") (pin "A") (pinfunction "A_A") (pintype "passive"))
      (node (ref "RN4") (pin "9") (pinfunction "9_9") (pintype "passive"))
    )
    (net (code "51") (name "VCC") (class "Default")
      (node (ref "GPO1") (pin "3") (pinfunction "1_3") (pintype "passive"))
      (node (ref "GPO2") (pin "3") (pinfunction "1_3") (pintype "passive"))
      (node (ref "GPO3") (pin "3") (pinfunction "1_3") (pintype "passive"))
      (node (ref "GPO4") (pin "3") (pinfunction "1_3") (pintype "passive"))
      (node (ref "GPO5") (pin "3") (pinfunction "1_3") (pintype "passive"))
      (node (ref "GPO6") (pin "3") (pinfunction "1_3") (pintype "passive"))
      (node (ref "GPO7") (pin "3") (pinfunction "1_3") (pintype "passive"))
      (node (ref "GPO8") (pin "3") (pinfunction "1_3") (pintype "passive"))
      (node (ref "R5") (pin "2") (pinfunction "2_2") (pintype "passive"))
      (node (ref "RN1") (pin "1") (pinfunction "1_1") (pintype "passive"))
      (node (ref "RN2") (pin "1") (pinfunction "1_1") (pintype "passive"))
      (node (ref "RN4") (pin "1") (pinfunction "1_1") (pintype "passive"))
      (node (ref "RN5") (pin "1") (pinfunction "1_1") (pintype "passive"))
      (node (ref "U$10") (pin "2") (pinfunction "2_2") (pintype "bidirectional"))
      (node (ref "U$11") (pin "2") (pinfunction "2_2") (pintype "bidirectional"))
      (node (ref "U$12") (pin "2") (pinfunction "2_2") (pintype "bidirectional"))
      (node (ref "U$13") (pin "2") (pinfunction "2_2") (pintype "bidirectional"))
      (node (ref "U$5") (pin "PWR") (pinfunction "PWR_PWR") (pintype "bidirectional"))
      (node (ref "U$6") (pin "2") (pinfunction "2_2") (pintype "bidirectional"))
      (node (ref "U$8") (pin "2") (pinfunction "2_2") (pintype "bidirectional"))
      (node (ref "U$9") (pin "2") (pinfunction "2_2") (pintype "bidirectional"))
    )
    (net (code "52") (name "unconnected-(U$11-Pad4)") (class "Default")
      (node (ref "U$11") (pin "4") (pinfunction "4_4") (pintype "bidirectional"))
    )
    (net (code "53") (name "unconnected-(U$11-Pad6)") (class "Default")
      (node (ref "U$11") (pin "6") (pinfunction "6_6") (pintype "bidirectional"))
    )
    (net (code "54") (name "unconnected-(U$11-Pad8)") (class "Default")
      (node (ref "U$11") (pin "8") (pinfunction "8_8") (pintype "bidirectional"))
    )
    (net (code "55") (name "unconnected-(U$12-Pad4)") (class "Default")
      (node (ref "U$12") (pin "4") (pinfunction "4_4") (pintype "bidirectional"))
    )
    (net (code "56") (name "unconnected-(U$12-Pad6)") (class "Default")
      (node (ref "U$12") (pin "6") (pinfunction "6_6") (pintype "bidirectional"))
    )
    (net (code "57") (name "unconnected-(U$12-Pad8)") (class "Default")
      (node (ref "U$12") (pin "8") (pinfunction "8_8") (pintype "bidirectional"))
    )
    (net (code "58") (name "unconnected-(U$13-Pad4)") (class "Default")
      (node (ref "U$13") (pin "4") (pinfunction "4_4") (pintype "bidirectional"))
    )
    (net (code "59") (name "unconnected-(U$13-Pad6)") (class "Default")
      (node (ref "U$13") (pin "6") (pinfunction "6_6") (pintype "bidirectional"))
    )
    (net (code "60") (name "unconnected-(U$13-Pad7)") (class "Default")
      (node (ref "U$13") (pin "7") (pinfunction "7_7") (pintype "bidirectional"))
    )
    (net (code "61") (name "unconnected-(U$13-Pad8)") (class "Default")
      (node (ref "U$13") (pin "8") (pinfunction "8_8") (pintype "bidirectional"))
    )
  )
)
